# coverter_board.net
KiCad netlist of a schematic drawn in EAGLE
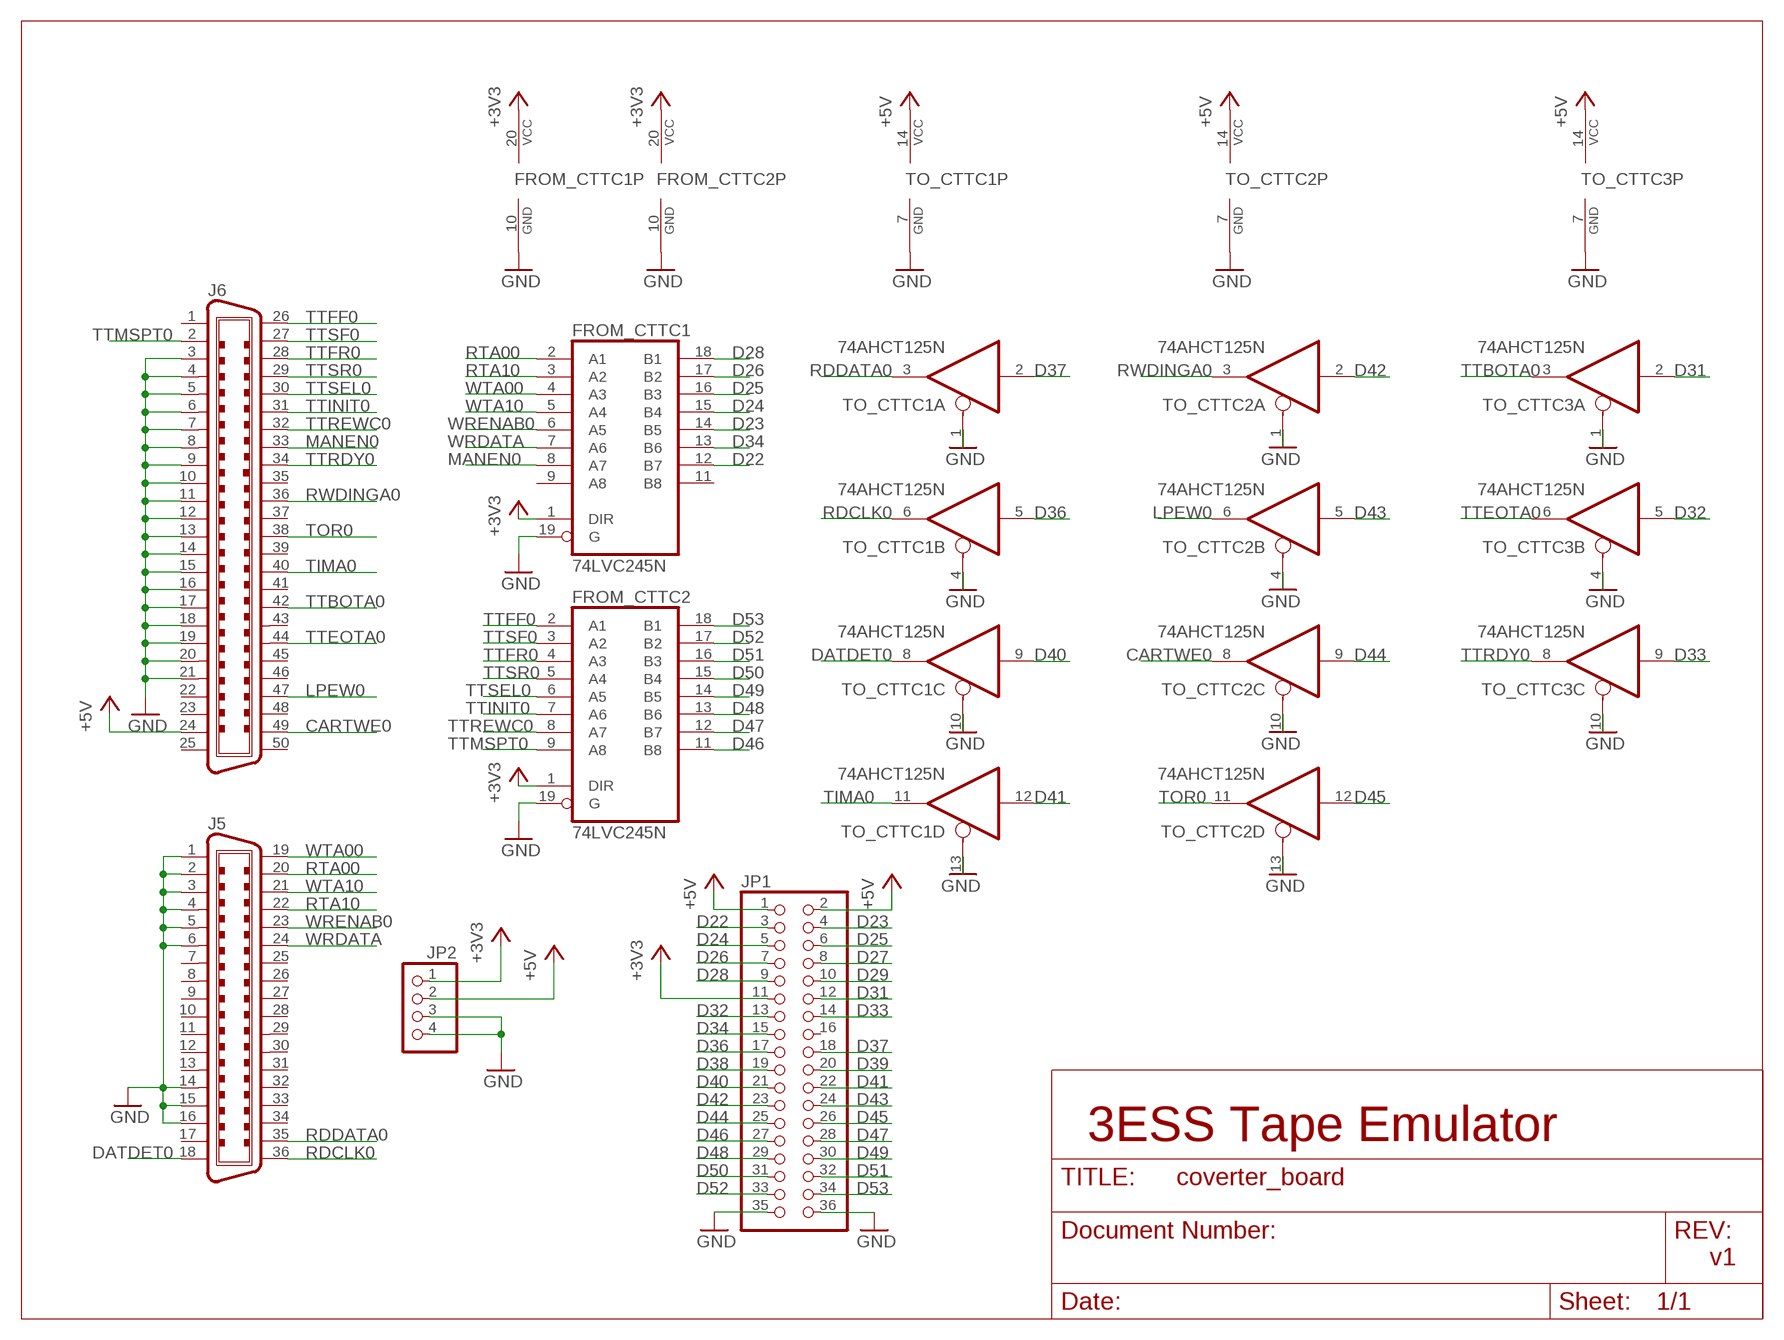
[diagram p0: schematic, sheet 1]

(export (version "E")
  (design (tool "Eeschema 10.0.6"))
  (components
    (comp (ref "FROM_CTTC1")
      (value "74LVC245N")
      (footprint "eagle-import:DIL20")
      (libsource (lib "eagle-import") (part "74245NLVC"))
    )
    (comp (ref "FROM_CTTC2")
      (value "74LVC245N")
      (footprint "eagle-import:DIL20")
      (libsource (lib "eagle-import") (part "74245NLVC"))
    )
    (comp (ref "J5")
      (value "C36V")
      (footprint "eagle-import:36V")
      (libsource (lib "eagle-import") (part "C36V"))
    )
    (comp (ref "J6")
      (value "C50V")
      (footprint "eagle-import:50V")
      (libsource (lib "eagle-import") (part "C50V"))
    )
    (comp (ref "JP1")
      (value "PINHD-2X18")
      (footprint "eagle-import:2X18")
      (libsource (lib "eagle-import") (part "PINHD-2X18"))
    )
    (comp (ref "JP2")
      (value "PINHD-1X4")
      (footprint "eagle-import:1X04")
      (libsource (lib "eagle-import") (part "PINHD-1X4"))
    )
    (comp (ref "TO_CTTC1")
      (value "74AHCT125N")
      (footprint "eagle-import:DIL14")
      (libsource (lib "eagle-import") (part "74125NAHCT"))
    )
    (comp (ref "TO_CTTC2")
      (value "74AHCT125N")
      (footprint "eagle-import:DIL14")
      (libsource (lib "eagle-import") (part "74125NAHCT"))
    )
    (comp (ref "TO_CTTC3")
      (value "74AHCT125N")
      (footprint "eagle-import:DIL14")
      (libsource (lib "eagle-import") (part "74125NAHCT"))
    )
  )
  (nets
    (net (code "1") (name "+3V3") (class "Default")
      (node (ref "FROM_CTTC1") (pin "1") (pinfunction "DIR_1") (pintype "input"))
      (node (ref "FROM_CTTC1") (pin "20") (pinfunction "VCC_20") (pintype "power_in"))
      (node (ref "FROM_CTTC2") (pin "1") (pinfunction "DIR_1") (pintype "input"))
      (node (ref "FROM_CTTC2") (pin "20") (pinfunction "VCC_20") (pintype "power_in"))
      (node (ref "JP1") (pin "11") (pinfunction "11_11") (pintype "passive"))
      (node (ref "JP2") (pin "1") (pinfunction "1_1") (pintype "passive"))
    )
    (net (code "2") (name "+5V") (class "Default")
      (node (ref "J6") (pin "24") (pinfunction "24_24") (pintype "passive"))
      (node (ref "JP1") (pin "1") (pinfunction "1_1") (pintype "passive"))
      (node (ref "JP1") (pin "2") (pinfunction "2_2") (pintype "passive"))
      (node (ref "JP2") (pin "2") (pinfunction "2_2") (pintype "passive"))
      (node (ref "TO_CTTC1") (pin "14") (pinfunction "VCC_14") (pintype "power_in"))
      (node (ref "TO_CTTC2") (pin "14") (pinfunction "VCC_14") (pintype "power_in"))
      (node (ref "TO_CTTC3") (pin "14") (pinfunction "VCC_14") (pintype "power_in"))
    )
    (net (code "3") (name "/CARTWE0") (class "Default")
      (node (ref "J6") (pin "49") (pinfunction "49_49") (pintype "passive"))
      (node (ref "TO_CTTC2") (pin "8") (pinfunction "O_8") (pintype "tri_state"))
    )
    (net (code "4") (name "/D22") (class "Default")
      (node (ref "FROM_CTTC1") (pin "12") (pinfunction "B7_12") (pintype "bidirectional"))
      (node (ref "JP1") (pin "3") (pinfunction "3_3") (pintype "passive"))
    )
    (net (code "5") (name "/D23") (class "Default")
      (node (ref "FROM_CTTC1") (pin "14") (pinfunction "B5_14") (pintype "bidirectional"))
      (node (ref "JP1") (pin "4") (pinfunction "4_4") (pintype "passive"))
    )
    (net (code "6") (name "/D24") (class "Default")
      (node (ref "FROM_CTTC1") (pin "15") (pinfunction "B4_15") (pintype "bidirectional"))
      (node (ref "JP1") (pin "5") (pinfunction "5_5") (pintype "passive"))
    )
    (net (code "7") (name "/D25") (class "Default")
      (node (ref "FROM_CTTC1") (pin "16") (pinfunction "B3_16") (pintype "bidirectional"))
      (node (ref "JP1") (pin "6") (pinfunction "6_6") (pintype "passive"))
    )
    (net (code "8") (name "/D26") (class "Default")
      (node (ref "FROM_CTTC1") (pin "17") (pinfunction "B2_17") (pintype "bidirectional"))
      (node (ref "JP1") (pin "7") (pinfunction "7_7") (pintype "passive"))
    )
    (net (code "9") (name "/D27") (class "Default")
      (node (ref "JP1") (pin "8") (pinfunction "8_8") (pintype "passive"))
    )
    (net (code "10") (name "/D28") (class "Default")
      (node (ref "FROM_CTTC1") (pin "18") (pinfunction "B1_18") (pintype "bidirectional"))
      (node (ref "JP1") (pin "9") (pinfunction "9_9") (pintype "passive"))
    )
    (net (code "11") (name "/D29") (class "Default")
      (node (ref "JP1") (pin "10") (pinfunction "10_10") (pintype "passive"))
    )
    (net (code "12") (name "/D31") (class "Default")
      (node (ref "JP1") (pin "12") (pinfunction "12_12") (pintype "passive"))
      (node (ref "TO_CTTC3") (pin "2") (pinfunction "I_2") (pintype "input"))
    )
    (net (code "13") (name "/D32") (class "Default")
      (node (ref "JP1") (pin "13") (pinfunction "13_13") (pintype "passive"))
      (node (ref "TO_CTTC3") (pin "5") (pinfunction "I_5") (pintype "input"))
    )
    (net (code "14") (name "/D33") (class "Default")
      (node (ref "JP1") (pin "14") (pinfunction "14_14") (pintype "passive"))
      (node (ref "TO_CTTC3") (pin "9") (pinfunction "I_9") (pintype "input"))
    )
    (net (code "15") (name "/D34") (class "Default")
      (node (ref "FROM_CTTC1") (pin "13") (pinfunction "B6_13") (pintype "bidirectional"))
      (node (ref "JP1") (pin "15") (pinfunction "15_15") (pintype "passive"))
    )
    (net (code "16") (name "/D36") (class "Default")
      (node (ref "JP1") (pin "17") (pinfunction "17_17") (pintype "passive"))
      (node (ref "TO_CTTC1") (pin "5") (pinfunction "I_5") (pintype "input"))
    )
    (net (code "17") (name "/D37") (class "Default")
      (node (ref "JP1") (pin "18") (pinfunction "18_18") (pintype "passive"))
      (node (ref "TO_CTTC1") (pin "2") (pinfunction "I_2") (pintype "input"))
    )
    (net (code "18") (name "/D38") (class "Default")
      (node (ref "JP1") (pin "19") (pinfunction "19_19") (pintype "passive"))
    )
    (net (code "19") (name "/D39") (class "Default")
      (node (ref "JP1") (pin "20") (pinfunction "20_20") (pintype "passive"))
    )
    (net (code "20") (name "/D40") (class "Default")
      (node (ref "JP1") (pin "21") (pinfunction "21_21") (pintype "passive"))
      (node (ref "TO_CTTC1") (pin "9") (pinfunction "I_9") (pintype "input"))
    )
    (net (code "21") (name "/D41") (class "Default")
      (node (ref "JP1") (pin "22") (pinfunction "22_22") (pintype "passive"))
      (node (ref "TO_CTTC1") (pin "12") (pinfunction "I_12") (pintype "input"))
    )
    (net (code "22") (name "/D42") (class "Default")
      (node (ref "JP1") (pin "23") (pinfunction "23_23") (pintype "passive"))
      (node (ref "TO_CTTC2") (pin "2") (pinfunction "I_2") (pintype "input"))
    )
    (net (code "23") (name "/D43") (class "Default")
      (node (ref "JP1") (pin "24") (pinfunction "24_24") (pintype "passive"))
      (node (ref "TO_CTTC2") (pin "5") (pinfunction "I_5") (pintype "input"))
    )
    (net (code "24") (name "/D44") (class "Default")
      (node (ref "JP1") (pin "25") (pinfunction "25_25") (pintype "passive"))
      (node (ref "TO_CTTC2") (pin "9") (pinfunction "I_9") (pintype "input"))
    )
    (net (code "25") (name "/D45") (class "Default")
      (node (ref "JP1") (pin "26") (pinfunction "26_26") (pintype "passive"))
      (node (ref "TO_CTTC2") (pin "12") (pinfunction "I_12") (pintype "input"))
    )
    (net (code "26") (name "/D46") (class "Default")
      (node (ref "FROM_CTTC2") (pin "11") (pinfunction "B8_11") (pintype "bidirectional"))
      (node (ref "JP1") (pin "27") (pinfunction "27_27") (pintype "passive"))
    )
    (net (code "27") (name "/D47") (class "Default")
      (node (ref "FROM_CTTC2") (pin "12") (pinfunction "B7_12") (pintype "bidirectional"))
      (node (ref "JP1") (pin "28") (pinfunction "28_28") (pintype "passive"))
    )
    (net (code "28") (name "/D48") (class "Default")
      (node (ref "FROM_CTTC2") (pin "13") (pinfunction "B6_13") (pintype "bidirectional"))
      (node (ref "JP1") (pin "29") (pinfunction "29_29") (pintype "passive"))
    )
    (net (code "29") (name "/D49") (class "Default")
      (node (ref "FROM_CTTC2") (pin "14") (pinfunction "B5_14") (pintype "bidirectional"))
      (node (ref "JP1") (pin "30") (pinfunction "30_30") (pintype "passive"))
    )
    (net (code "30") (name "/D50") (class "Default")
      (node (ref "FROM_CTTC2") (pin "15") (pinfunction "B4_15") (pintype "bidirectional"))
      (node (ref "JP1") (pin "31") (pinfunction "31_31") (pintype "passive"))
    )
    (net (code "31") (name "/D51") (class "Default")
      (node (ref "FROM_CTTC2") (pin "16") (pinfunction "B3_16") (pintype "bidirectional"))
      (node (ref "JP1") (pin "32") (pinfunction "32_32") (pintype "passive"))
    )
    (net (code "32") (name "/D52") (class "Default")
      (node (ref "FROM_CTTC2") (pin "17") (pinfunction "B2_17") (pintype "bidirectional"))
      (node (ref "JP1") (pin "33") (pinfunction "33_33") (pintype "passive"))
    )
    (net (code "33") (name "/D53") (class "Default")
      (node (ref "FROM_CTTC2") (pin "18") (pinfunction "B1_18") (pintype "bidirectional"))
      (node (ref "JP1") (pin "34") (pinfunction "34_34") (pintype "passive"))
    )
    (net (code "34") (name "/DATDET0") (class "Default")
      (node (ref "J5") (pin "18") (pinfunction "18_18") (pintype "passive"))
      (node (ref "TO_CTTC1") (pin "8") (pinfunction "O_8") (pintype "tri_state"))
    )
    (net (code "35") (name "/LPEW0") (class "Default")
      (node (ref "J6") (pin "47") (pinfunction "47_47") (pintype "passive"))
      (node (ref "TO_CTTC2") (pin "6") (pinfunction "O_6") (pintype "tri_state"))
    )
    (net (code "36") (name "/MANEN0") (class "Default")
      (node (ref "FROM_CTTC1") (pin "8") (pinfunction "A7_8") (pintype "bidirectional"))
      (node (ref "J6") (pin "33") (pinfunction "33_33") (pintype "passive"))
    )
    (net (code "37") (name "/RDCLK0") (class "Default")
      (node (ref "J5") (pin "36") (pinfunction "36_36") (pintype "passive"))
      (node (ref "TO_CTTC1") (pin "6") (pinfunction "O_6") (pintype "tri_state"))
    )
    (net (code "38") (name "/RDDATA0") (class "Default")
      (node (ref "J5") (pin "35") (pinfunction "35_35") (pintype "passive"))
      (node (ref "TO_CTTC1") (pin "3") (pinfunction "O_3") (pintype "tri_state"))
    )
    (net (code "39") (name "/RTA00") (class "Default")
      (node (ref "FROM_CTTC1") (pin "2") (pinfunction "A1_2") (pintype "bidirectional"))
      (node (ref "J5") (pin "20") (pinfunction "20_20") (pintype "passive"))
    )
    (net (code "40") (name "/RTA10") (class "Default")
      (node (ref "FROM_CTTC1") (pin "3") (pinfunction "A2_3") (pintype "bidirectional"))
      (node (ref "J5") (pin "22") (pinfunction "22_22") (pintype "passive"))
    )
    (net (code "41") (name "/RWDINGA0") (class "Default")
      (node (ref "J6") (pin "36") (pinfunction "36_36") (pintype "passive"))
      (node (ref "TO_CTTC2") (pin "3") (pinfunction "O_3") (pintype "tri_state"))
    )
    (net (code "42") (name "/TIMA0") (class "Default")
      (node (ref "J6") (pin "40") (pinfunction "40_40") (pintype "passive"))
      (node (ref "TO_CTTC1") (pin "11") (pinfunction "O_11") (pintype "tri_state"))
    )
    (net (code "43") (name "/TOR0") (class "Default")
      (node (ref "J6") (pin "38") (pinfunction "38_38") (pintype "passive"))
      (node (ref "TO_CTTC2") (pin "11") (pinfunction "O_11") (pintype "tri_state"))
    )
    (net (code "44") (name "/TTBOTA0") (class "Default")
      (node (ref "J6") (pin "42") (pinfunction "42_42") (pintype "passive"))
      (node (ref "TO_CTTC3") (pin "3") (pinfunction "O_3") (pintype "tri_state"))
    )
    (net (code "45") (name "/TTEOTA0") (class "Default")
      (node (ref "J6") (pin "44") (pinfunction "44_44") (pintype "passive"))
      (node (ref "TO_CTTC3") (pin "6") (pinfunction "O_6") (pintype "tri_state"))
    )
    (net (code "46") (name "/TTFF0") (class "Default")
      (node (ref "FROM_CTTC2") (pin "2") (pinfunction "A1_2") (pintype "bidirectional"))
      (node (ref "J6") (pin "26") (pinfunction "26_26") (pintype "passive"))
    )
    (net (code "47") (name "/TTFR0") (class "Default")
      (node (ref "FROM_CTTC2") (pin "4") (pinfunction "A3_4") (pintype "bidirectional"))
      (node (ref "J6") (pin "28") (pinfunction "28_28") (pintype "passive"))
    )
    (net (code "48") (name "/TTINIT0") (class "Default")
      (node (ref "FROM_CTTC2") (pin "7") (pinfunction "A6_7") (pintype "bidirectional"))
      (node (ref "J6") (pin "31") (pinfunction "31_31") (pintype "passive"))
    )
    (net (code "49") (name "/TTMSPT0") (class "Default")
      (node (ref "FROM_CTTC2") (pin "9") (pinfunction "A8_9") (pintype "bidirectional"))
      (node (ref "J6") (pin "2") (pinfunction "2_2") (pintype "passive"))
    )
    (net (code "50") (name "/TTRDY0") (class "Default")
      (node (ref "J6") (pin "34") (pinfunction "34_34") (pintype "passive"))
      (node (ref "TO_CTTC3") (pin "8") (pinfunction "O_8") (pintype "tri_state"))
    )
    (net (code "51") (name "/TTREWC0") (class "Default")
      (node (ref "FROM_CTTC2") (pin "8") (pinfunction "A7_8") (pintype "bidirectional"))
      (node (ref "J6") (pin "32") (pinfunction "32_32") (pintype "passive"))
    )
    (net (code "52") (name "/TTSEL0") (class "Default")
      (node (ref "FROM_CTTC2") (pin "6") (pinfunction "A5_6") (pintype "bidirectional"))
      (node (ref "J6") (pin "30") (pinfunction "30_30") (pintype "passive"))
    )
    (net (code "53") (name "/TTSF0") (class "Default")
      (node (ref "FROM_CTTC2") (pin "3") (pinfunction "A2_3") (pintype "bidirectional"))
      (node (ref "J6") (pin "27") (pinfunction "27_27") (pintype "passive"))
    )
    (net (code "54") (name "/TTSR0") (class "Default")
      (node (ref "FROM_CTTC2") (pin "5") (pinfunction "A4_5") (pintype "bidirectional"))
      (node (ref "J6") (pin "29") (pinfunction "29_29") (pintype "passive"))
    )
    (net (code "55") (name "/WRDATA") (class "Default")
      (node (ref "FROM_CTTC1") (pin "7") (pinfunction "A6_7") (pintype "bidirectional"))
      (node (ref "J5") (pin "24") (pinfunction "24_24") (pintype "passive"))
    )
    (net (code "56") (name "/WRENAB0") (class "Default")
      (node (ref "FROM_CTTC1") (pin "6") (pinfunction "A5_6") (pintype "bidirectional"))
      (node (ref "J5") (pin "23") (pinfunction "23_23") (pintype "passive"))
    )
    (net (code "57") (name "/WTA00") (class "Default")
      (node (ref "FROM_CTTC1") (pin "4") (pinfunction "A3_4") (pintype "bidirectional"))
      (node (ref "J5") (pin "19") (pinfunction "19_19") (pintype "passive"))
    )
    (net (code "58") (name "/WTA10") (class "Default")
      (node (ref "FROM_CTTC1") (pin "5") (pinfunction "A4_5") (pintype "bidirectional"))
      (node (ref "J5") (pin "21") (pinfunction "21_21") (pintype "passive"))
    )
    (net (code "59") (name "GND") (class "Default")
      (node (ref "FROM_CTTC1") (pin "10") (pinfunction "GND_10") (pintype "power_in"))
      (node (ref "FROM_CTTC1") (pin "19") (pinfunction "G_19") (pintype "input"))
      (node (ref "FROM_CTTC2") (pin "10") (pinfunction "GND_10") (pintype "power_in"))
      (node (ref "FROM_CTTC2") (pin "19") (pinfunction "G_19") (pintype "input"))
      (node (ref "J5") (pin "1") (pinfunction "1_1") (pintype "passive"))
      (node (ref "J5") (pin "14") (pinfunction "14_14") (pintype "passive"))
      (node (ref "J5") (pin "15") (pinfunction "15_15") (pintype "passive"))
      (node (ref "J5") (pin "16") (pinfunction "16_16") (pintype "passive"))
      (node (ref "J5") (pin "2") (pinfunction "2_2") (pintype "passive"))
      (node (ref "J5") (pin "3") (pinfunction "3_3") (pintype "passive"))
      (node (ref "J5") (pin "4") (pinfunction "4_4") (pintype "passive"))
      (node (ref "J5") (pin "5") (pinfunction "5_5") (pintype "passive"))
      (node (ref "J5") (pin "6") (pinfunction "6_6") (pintype "passive"))
      (node (ref "J6") (pin "10") (pinfunction "10_10") (pintype "passive"))
      (node (ref "J6") (pin "11") (pinfunction "11_11") (pintype "passive"))
      (node (ref "J6") (pin "12") (pinfunction "12_12") (pintype "passive"))
      (node (ref "J6") (pin "13") (pinfunction "13_13") (pintype "passive"))
      (node (ref "J6") (pin "14") (pinfunction "14_14") (pintype "passive"))
      (node (ref "J6") (pin "15") (pinfunction "15_15") (pintype "passive"))
      (node (ref "J6") (pin "16") (pinfunction "16_16") (pintype "passive"))
      (node (ref "J6") (pin "17") (pinfunction "17_17") (pintype "passive"))
      (node (ref "J6") (pin "18") (pinfunction "18_18") (pintype "passive"))
      (node (ref "J6") (pin "19") (pinfunction "19_19") (pintype "passive"))
      (node (ref "J6") (pin "20") (pinfunction "20_20") (pintype "passive"))
      (node (ref "J6") (pin "21") (pinfunction "21_21") (pintype "passive"))
      (node (ref "J6") (pin "3") (pinfunction "3_3") (pintype "passive"))
      (node (ref "J6") (pin "4") (pinfunction "4_4") (pintype "passive"))
      (node (ref "J6") (pin "5") (pinfunction "5_5") (pintype "passive"))
      (node (ref "J6") (pin "6") (pinfunction "6_6") (pintype "passive"))
      (node (ref "J6") (pin "7") (pinfunction "7_7") (pintype "passive"))
      (node (ref "J6") (pin "8") (pinfunction "8_8") (pintype "passive"))
      (node (ref "J6") (pin "9") (pinfunction "9_9") (pintype "passive"))
      (node (ref "JP1") (pin "35") (pinfunction "35_35") (pintype "passive"))
      (node (ref "JP1") (pin "36") (pinfunction "36_36") (pintype "passive"))
      (node (ref "JP2") (pin "3") (pinfunction "3_3") (pintype "passive"))
      (node (ref "JP2") (pin "4") (pinfunction "4_4") (pintype "passive"))
      (node (ref "TO_CTTC1") (pin "1") (pinfunction "OE_1") (pintype "input"))
      (node (ref "TO_CTTC1") (pin "10") (pinfunction "OE_10") (pintype "input"))
      (node (ref "TO_CTTC1") (pin "13") (pinfunction "OE_13") (pintype "input"))
      (node (ref "TO_CTTC1") (pin "4") (pinfunction "OE_4") (pintype "input"))
      (node (ref "TO_CTTC1") (pin "7") (pinfunction "GND_7") (pintype "power_in"))
      (node (ref "TO_CTTC2") (pin "1") (pinfunction "OE_1") (pintype "input"))
      (node (ref "TO_CTTC2") (pin "10") (pinfunction "OE_10") (pintype "input"))
      (node (ref "TO_CTTC2") (pin "13") (pinfunction "OE_13") (pintype "input"))
      (node (ref "TO_CTTC2") (pin "4") (pinfunction "OE_4") (pintype "input"))
      (node (ref "TO_CTTC2") (pin "7") (pinfunction "GND_7") (pintype "power_in"))
      (node (ref "TO_CTTC3") (pin "1") (pinfunction "OE_1") (pintype "input"))
      (node (ref "TO_CTTC3") (pin "10") (pinfunction "OE_10") (pintype "input"))
      (node (ref "TO_CTTC3") (pin "4") (pinfunction "OE_4") (pintype "input"))
      (node (ref "TO_CTTC3") (pin "7") (pinfunction "GND_7") (pintype "power_in"))
    )
    (net (code "60") (name "unconnected-(FROM_CTTC1A-A8-Pad9)") (class "Default")
      (node (ref "FROM_CTTC1") (pin "9") (pinfunction "A8_9") (pintype "bidirectional"))
    )
    (net (code "61") (name "unconnected-(FROM_CTTC1A-B8-Pad11)") (class "Default")
      (node (ref "FROM_CTTC1") (pin "11") (pinfunction "B8_11") (pintype "bidirectional"))
    )
    (net (code "62") (name "unconnected-(J5-Pad7)") (class "Default")
      (node (ref "J5") (pin "7") (pinfunction "7_7") (pintype "passive"))
    )
    (net (code "63") (name "unconnected-(J5-Pad8)") (class "Default")
      (node (ref "J5") (pin "8") (pinfunction "8_8") (pintype "passive"))
    )
    (net (code "64") (name "unconnected-(J5-Pad9)") (class "Default")
      (node (ref "J5") (pin "9") (pinfunction "9_9") (pintype "passive"))
    )
    (net (code "65") (name "unconnected-(J5-Pad10)") (class "Default")
      (node (ref "J5") (pin "10") (pinfunction "10_10") (pintype "passive"))
    )
    (net (code "66") (name "unconnected-(J5-Pad11)") (class "Default")
      (node (ref "J5") (pin "11") (pinfunction "11_11") (pintype "passive"))
    )
    (net (code "67") (name "unconnected-(J5-Pad12)") (class "Default")
      (node (ref "J5") (pin "12") (pinfunction "12_12") (pintype "passive"))
    )
    (net (code "68") (name "unconnected-(J5-Pad13)") (class "Default")
      (node (ref "J5") (pin "13") (pinfunction "13_13") (pintype "passive"))
    )
    (net (code "69") (name "unconnected-(J5-Pad17)") (class "Default")
      (node (ref "J5") (pin "17") (pinfunction "17_17") (pintype "passive"))
    )
    (net (code "70") (name "unconnected-(J5-Pad25)") (class "Default")
      (node (ref "J5") (pin "25") (pinfunction "25_25") (pintype "passive"))
    )
    (net (code "71") (name "unconnected-(J5-Pad26)") (class "Default")
      (node (ref "J5") (pin "26") (pinfunction "26_26") (pintype "passive"))
    )
    (net (code "72") (name "unconnected-(J5-Pad27)") (class "Default")
      (node (ref "J5") (pin "27") (pinfunction "27_27") (pintype "passive"))
    )
    (net (code "73") (name "unconnected-(J5-Pad28)") (class "Default")
      (node (ref "J5") (pin "28") (pinfunction "28_28") (pintype "passive"))
    )
    (net (code "74") (name "unconnected-(J5-Pad29)") (class "Default")
      (node (ref "J5") (pin "29") (pinfunction "29_29") (pintype "passive"))
    )
    (net (code "75") (name "unconnected-(J5-Pad30)") (class "Default")
      (node (ref "J5") (pin "30") (pinfunction "30_30") (pintype "passive"))
    )
    (net (code "76") (name "unconnected-(J5-Pad31)") (class "Default")
      (node (ref "J5") (pin "31") (pinfunction "31_31") (pintype "passive"))
    )
    (net (code "77") (name "unconnected-(J5-Pad32)") (class "Default")
      (node (ref "J5") (pin "32") (pinfunction "32_32") (pintype "passive"))
    )
    (net (code "78") (name "unconnected-(J5-Pad33)") (class "Default")
      (node (ref "J5") (pin "33") (pinfunction "33_33") (pintype "passive"))
    )
    (net (code "79") (name "unconnected-(J5-Pad34)") (class "Default")
      (node (ref "J5") (pin "34") (pinfunction "34_34") (pintype "passive"))
    )
    (net (code "80") (name "unconnected-(J6-Pad1)") (class "Default")
      (node (ref "J6") (pin "1") (pinfunction "1_1") (pintype "passive"))
    )
    (net (code "81") (name "unconnected-(J6-Pad22)") (class "Default")
      (node (ref "J6") (pin "22") (pinfunction "22_22") (pintype "passive"))
    )
    (net (code "82") (name "unconnected-(J6-Pad23)") (class "Default")
      (node (ref "J6") (pin "23") (pinfunction "23_23") (pintype "passive"))
    )
    (net (code "83") (name "unconnected-(J6-Pad25)") (class "Default")
      (node (ref "J6") (pin "25") (pinfunction "25_25") (pintype "passive"))
    )
    (net (code "84") (name "unconnected-(J6-Pad35)") (class "Default")
      (node (ref "J6") (pin "35") (pinfunction "35_35") (pintype "passive"))
    )
    (net (code "85") (name "unconnected-(J6-Pad37)") (class "Default")
      (node (ref "J6") (pin "37") (pinfunction "37_37") (pintype "passive"))
    )
    (net (code "86") (name "unconnected-(J6-Pad39)") (class "Default")
      (node (ref "J6") (pin "39") (pinfunction "39_39") (pintype "passive"))
    )
    (net (code "87") (name "unconnected-(J6-Pad41)") (class "Default")
      (node (ref "J6") (pin "41") (pinfunction "41_41") (pintype "passive"))
    )
    (net (code "88") (name "unconnected-(J6-Pad43)") (class "Default")
      (node (ref "J6") (pin "43") (pinfunction "43_43") (pintype "passive"))
    )
    (net (code "89") (name "unconnected-(J6-Pad45)") (class "Default")
      (node (ref "J6") (pin "45") (pinfunction "45_45") (pintype "passive"))
    )
    (net (code "90") (name "unconnected-(J6-Pad46)") (class "Default")
      (node (ref "J6") (pin "46") (pinfunction "46_46") (pintype "passive"))
    )
    (net (code "91") (name "unconnected-(J6-Pad48)") (class "Default")
      (node (ref "J6") (pin "48") (pinfunction "48_48") (pintype "passive"))
    )
    (net (code "92") (name "unconnected-(J6-Pad50)") (class "Default")
      (node (ref "J6") (pin "50") (pinfunction "50_50") (pintype "passive"))
    )
    (net (code "93") (name "unconnected-(JP1-Pad16)") (class "Default")
      (node (ref "JP1") (pin "16") (pinfunction "16_16") (pintype "passive"))
    )
  )
)
